# Main-Unit-Schematic.net
KiCad netlist of a schematic drawn in EAGLE
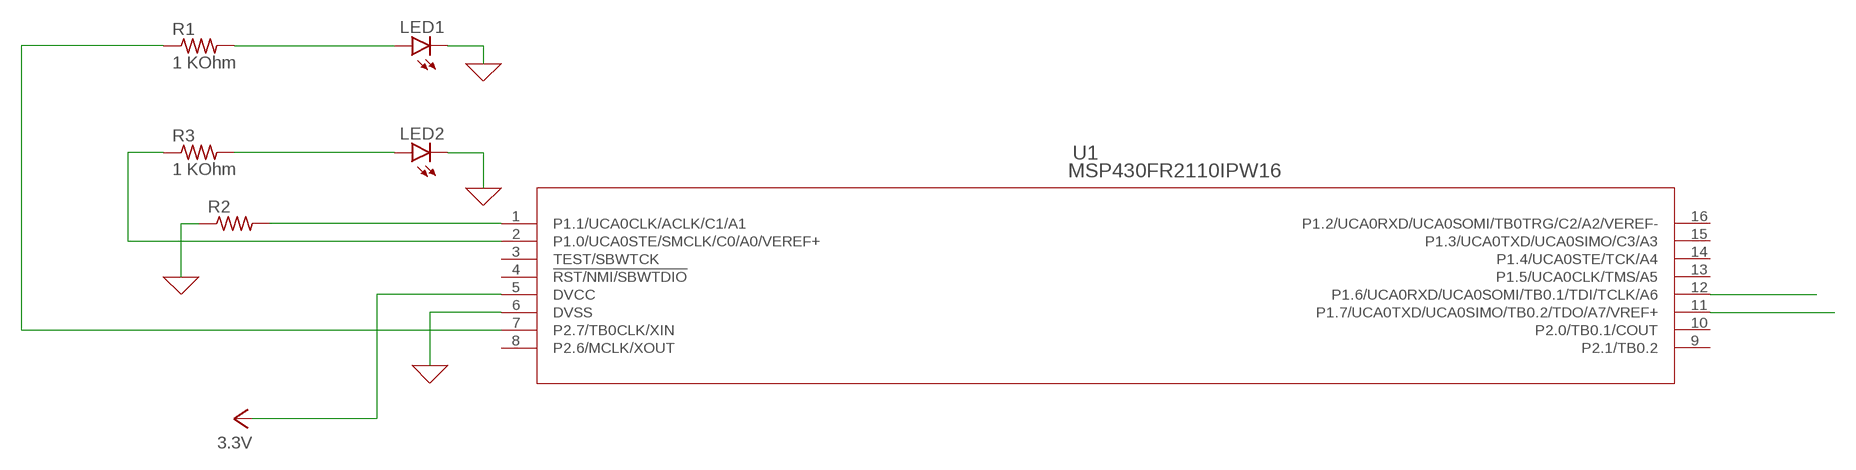
[diagram p0: schematic, sheet 1]

(export (version "E")
  (design (tool "Eeschema 10.0.6"))
  (components
    (comp (ref "LED1")
      (value "LED5MM")
      (footprint "eagle-import:LED5MM")
      (libsource (lib "eagle-import") (part "LED5MM"))
    )
    (comp (ref "LED2")
      (value "LED5MM")
      (footprint "eagle-import:LED5MM")
      (libsource (lib "eagle-import") (part "LED5MM"))
    )
    (comp (ref "R1")
      (value "1 KOhm")
      (footprint "eagle-import:0204_7")
      (libsource (lib "eagle-import") (part "R-US_0204/7"))
    )
    (comp (ref "R2")
      (value "R-US_0204/7")
      (footprint "eagle-import:0204_7")
      (libsource (lib "eagle-import") (part "R-US_0204/7"))
    )
    (comp (ref "R3")
      (value "1 KOhm")
      (footprint "eagle-import:0204_7")
      (libsource (lib "eagle-import") (part "R-US_0204/7"))
    )
    (comp (ref "U1")
      (value "MSP430FR2110IPW16")
      (footprint "eagle-import:PW16_TEX")
      (fields (field (name "COPYRIGHT") "Copyright (C) 2023 Ultra Librarian. All rights reserved."))
      (libsource (lib "eagle-import") (part "MSP430FR2110IPW16"))
    )
  )
  (nets
    (net (code "1") (name "3.3V") (class "Default")
      (node (ref "U1") (pin "5") (pinfunction "DVCC_5") (pintype "power_in"))
    )
    (net (code "2") (name "GND") (class "Default")
      (node (ref "LED1") (pin "K") (pinfunction "C_K") (pintype "passive"))
      (node (ref "LED2") (pin "K") (pinfunction "C_K") (pintype "passive"))
      (node (ref "R2") (pin "1") (pinfunction "1_1") (pintype "passive"))
      (node (ref "U1") (pin "6") (pinfunction "DVSS_6") (pintype "passive"))
    )
    (net (code "3") (name "Net-(LED1-PadA)") (class "Default")
      (node (ref "LED1") (pin "A") (pinfunction "A_A") (pintype "passive"))
      (node (ref "R1") (pin "2") (pinfunction "2_2") (pintype "passive"))
    )
    (net (code "4") (name "Net-(LED2-PadA)") (class "Default")
      (node (ref "LED2") (pin "A") (pinfunction "A_A") (pintype "passive"))
      (node (ref "R3") (pin "2") (pinfunction "2_2") (pintype "passive"))
    )
    (net (code "5") (name "Net-(U1-P1.0{slash}UCA0STE{slash}SMCLK{slash}C0{slash}A0{slash}VEREF+)") (class "Default")
      (node (ref "R3") (pin "1") (pinfunction "1_1") (pintype "passive"))
      (node (ref "U1") (pin "2") (pinfunction "P1.0/UCA0STE/SMCLK/C0/A0/VEREF+_2") (pintype "bidirectional"))
    )
    (net (code "6") (name "Net-(U1-P1.1{slash}UCA0CLK{slash}ACLK{slash}C1{slash}A1)") (class "Default")
      (node (ref "R2") (pin "2") (pinfunction "2_2") (pintype "passive"))
      (node (ref "U1") (pin "1") (pinfunction "P1.1/UCA0CLK/ACLK/C1/A1_1") (pintype "bidirectional"))
    )
    (net (code "7") (name "Net-(U1-P2.7{slash}TB0CLK{slash}XIN)") (class "Default")
      (node (ref "R1") (pin "1") (pinfunction "1_1") (pintype "passive"))
      (node (ref "U1") (pin "7") (pinfunction "P2.7/TB0CLK/XIN_7") (pintype "bidirectional"))
    )
    (net (code "8") (name "unconnected-(U1-P1.2{slash}UCA0RXD{slash}UCA0SOMI{slash}TB0TRG{slash}C2{slash}A2{slash}VEREF--Pad16)") (class "Default")
      (node (ref "U1") (pin "16") (pinfunction "P1.2/UCA0RXD/UCA0SOMI/TB0TRG/C2/A2/VEREF-_16") (pintype "bidirectional"))
    )
    (net (code "9") (name "unconnected-(U1-P1.3{slash}UCA0TXD{slash}UCA0SIMO{slash}C3{slash}A3-Pad15)") (class "Default")
      (node (ref "U1") (pin "15") (pinfunction "P1.3/UCA0TXD/UCA0SIMO/C3/A3_15") (pintype "bidirectional"))
    )
    (net (code "10") (name "unconnected-(U1-P1.4{slash}UCA0STE{slash}TCK{slash}A4-Pad14)") (class "Default")
      (node (ref "U1") (pin "14") (pinfunction "P1.4/UCA0STE/TCK/A4_14") (pintype "bidirectional"))
    )
    (net (code "11") (name "unconnected-(U1-P1.5{slash}UCA0CLK{slash}TMS{slash}A5-Pad13)") (class "Default")
      (node (ref "U1") (pin "13") (pinfunction "P1.5/UCA0CLK/TMS/A5_13") (pintype "bidirectional"))
    )
    (net (code "12") (name "unconnected-(U1-P1.6{slash}UCA0RXD{slash}UCA0SOMI{slash}TB0.1{slash}TDI{slash}TCLK{slash}A6-Pad12)") (class "Default")
      (node (ref "U1") (pin "12") (pinfunction "P1.6/UCA0RXD/UCA0SOMI/TB0.1/TDI/TCLK/A6_12") (pintype "bidirectional"))
    )
    (net (code "13") (name "unconnected-(U1-P1.7{slash}UCA0TXD{slash}UCA0SIMO{slash}TB0.2{slash}TDO{slash}A7{slash}VREF+-Pad11)") (class "Default")
      (node (ref "U1") (pin "11") (pinfunction "P1.7/UCA0TXD/UCA0SIMO/TB0.2/TDO/A7/VREF+_11") (pintype "bidirectional"))
    )
    (net (code "14") (name "unconnected-(U1-P2.0{slash}TB0.1{slash}COUT-Pad10)") (class "Default")
      (node (ref "U1") (pin "10") (pinfunction "P2.0/TB0.1/COUT_10") (pintype "bidirectional"))
    )
    (net (code "15") (name "unconnected-(U1-P2.1{slash}TB0.2-Pad9)") (class "Default")
      (node (ref "U1") (pin "9") (pinfunction "P2.1/TB0.2_9") (pintype "bidirectional"))
    )
    (net (code "16") (name "unconnected-(U1-P2.6{slash}MCLK{slash}XOUT-Pad8)") (class "Default")
      (node (ref "U1") (pin "8") (pinfunction "P2.6/MCLK/XOUT_8") (pintype "bidirectional"))
    )
    (net (code "17") (name "unconnected-(U1-TEST{slash}SBWTCK-Pad3)") (class "Default")
      (node (ref "U1") (pin "3") (pinfunction "TEST/SBWTCK_3") (pintype "input"))
    )
    (net (code "18") (name "unconnected-(U1-~{RST{slash}NMI{slash}SBWTDIO}-Pad4)") (class "Default")
      (node (ref "U1") (pin "4") (pinfunction "~{RST/NMI/SBWTDIO}_4") (pintype "bidirectional"))
    )
  )
)
